# utilidong-ftdi-uart-mk-2_1.net
KiCad netlist of a schematic drawn in EAGLE
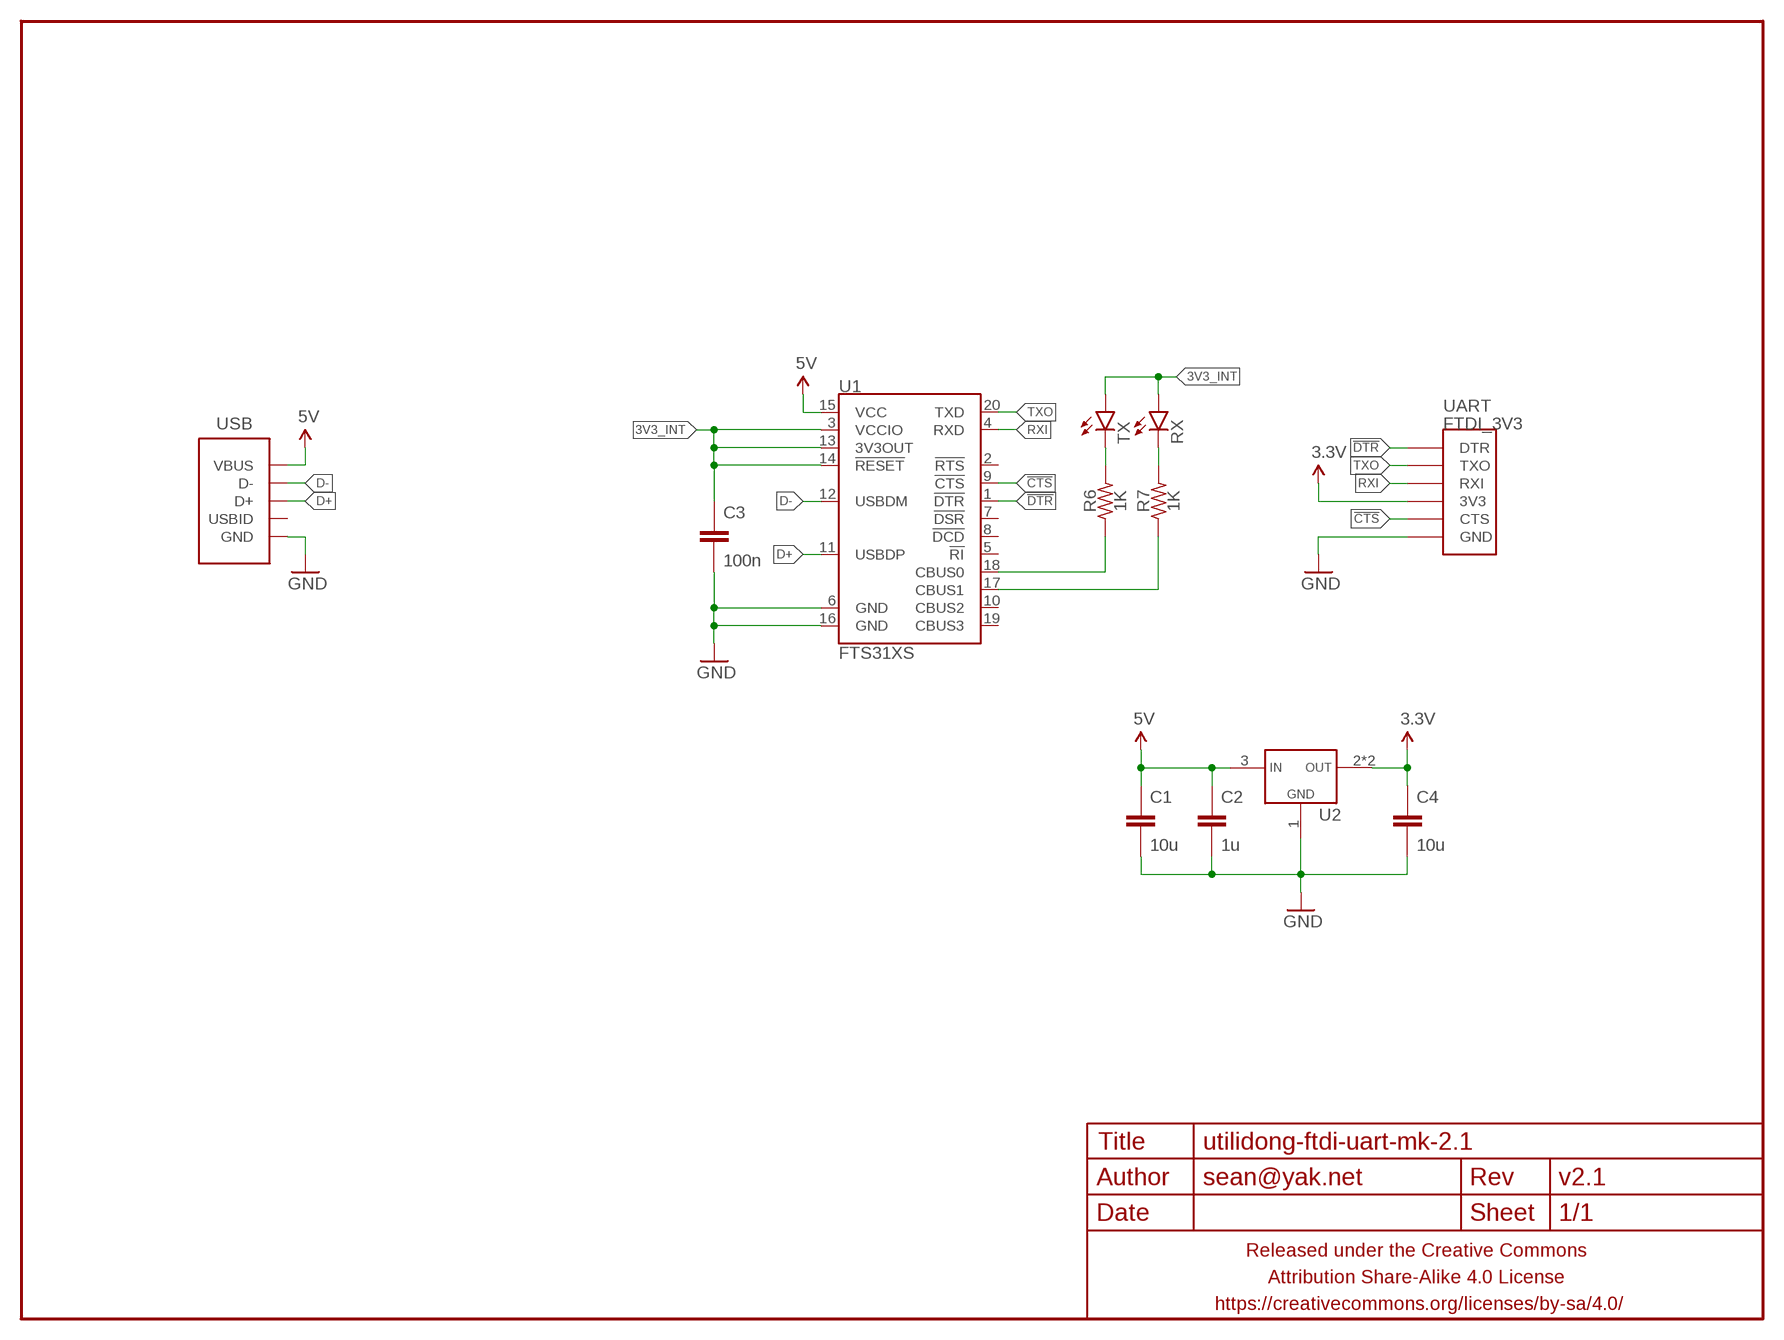
[diagram p0: schematic, sheet 1]

(export (version "E")
  (design (tool "Eeschema 10.0.6"))
  (components
    (comp (ref "C1")
      (value "10u")
      (footprint "eagle-import:C0805")
      (libsource (lib "eagle-import") (part "CAPACITOR-CERAMICC0805"))
    )
    (comp (ref "C2")
      (value "1u")
      (footprint "eagle-import:C0603")
      (libsource (lib "eagle-import") (part "CAPACITOR-CERAMICC0603"))
    )
    (comp (ref "C3")
      (value "100n")
      (footprint "eagle-import:C0603")
      (libsource (lib "eagle-import") (part "CAPACITOR-CERAMICC0603"))
    )
    (comp (ref "C4")
      (value "10u")
      (footprint "eagle-import:C0805")
      (libsource (lib "eagle-import") (part "CAPACITOR-CERAMICC0805"))
    )
    (comp (ref "FRAME1")
      (value "FRAME-LETTERNO_PACKAGE")
      (footprint "eagle-import:DUMMY")
      (fields (field (name "DESIGNER") "sean@yak.net") (field (name "VERSION") "v2.1"))
      (libsource (lib "eagle-import") (part "FRAME-LETTERNO_PACKAGE"))
    )
    (comp (ref "R6")
      (value "1K")
      (footprint "eagle-import:R0603")
      (libsource (lib "eagle-import") (part "RESISTORR0603"))
    )
    (comp (ref "R7")
      (value "1K")
      (footprint "eagle-import:R0603")
      (libsource (lib "eagle-import") (part "RESISTORR0603"))
    )
    (comp (ref "RX")
      (value "LED0603")
      (footprint "eagle-import:LED-0603")
      (libsource (lib "eagle-import") (part "LED0603"))
    )
    (comp (ref "TX")
      (value "LED0603")
      (footprint "eagle-import:LED-0603")
      (libsource (lib "eagle-import") (part "LED0603"))
    )
    (comp (ref "U1")
      (value "FTS31XS")
      (footprint "eagle-import:SSOP20_L")
      (libsource (lib "eagle-import") (part "FT231XS"))
    )
    (comp (ref "U2")
      (value "VREG_1117SOT89")
      (footprint "eagle-import:SOT89")
      (libsource (lib "eagle-import") (part "VREG_1117SOT89"))
    )
    (comp (ref "UART")
      (value "FTDI_3V3")
      (footprint "eagle-import:FTDI_3V3")
      (libsource (lib "eagle-import") (part "FTDI_3V3"))
    )
    (comp (ref "USB")
      (value "USB-ABFCI-10103594-USB-MICRO-B-LESS")
      (footprint "eagle-import:FCI-10103594-USB-MICRO-B-LESS")
      (libsource (lib "eagle-import") (part "USB-ABFCI-10103594-USB-MICRO-B-LESS"))
    )
  )
  (nets
    (net (code "1") (name "/~{CTS}") (class "Default")
      (node (ref "U1") (pin "9") (pinfunction "~{CTS}_9") (pintype "bidirectional"))
      (node (ref "UART") (pin "P$5") (pinfunction "CTS_P$5") (pintype "bidirectional"))
    )
    (net (code "2") (name "/~{DTR}") (class "Default")
      (node (ref "U1") (pin "1") (pinfunction "~{DTR}_1") (pintype "bidirectional"))
      (node (ref "UART") (pin "P$1") (pinfunction "DTR_P$1") (pintype "bidirectional"))
    )
    (net (code "3") (name "3.3V") (class "Default")
      (node (ref "C4") (pin "1") (pinfunction "1_1") (pintype "passive"))
      (node (ref "U2") (pin "2") (pinfunction "VOUT_2") (pintype "bidirectional"))
      (node (ref "U2") (pin "4") (pinfunction "VOUT_4") (pintype "bidirectional"))
      (node (ref "UART") (pin "P$4") (pinfunction "3V3_P$4") (pintype "bidirectional"))
    )
    (net (code "4") (name "3V3_INT") (class "Default")
      (node (ref "C3") (pin "1") (pinfunction "1_1") (pintype "passive"))
      (node (ref "RX") (pin "A") (pinfunction "A_A") (pintype "passive"))
      (node (ref "TX") (pin "A") (pinfunction "A_A") (pintype "passive"))
      (node (ref "U1") (pin "13") (pinfunction "3V3OUT_13") (pintype "bidirectional"))
      (node (ref "U1") (pin "14") (pinfunction "~{RESET}_14") (pintype "bidirectional"))
      (node (ref "U1") (pin "3") (pinfunction "VCCIO_3") (pintype "bidirectional"))
    )
    (net (code "5") (name "5V") (class "Default")
      (node (ref "C1") (pin "1") (pinfunction "1_1") (pintype "passive"))
      (node (ref "C2") (pin "1") (pinfunction "1_1") (pintype "passive"))
      (node (ref "U1") (pin "15") (pinfunction "VCC_15") (pintype "bidirectional"))
      (node (ref "U2") (pin "3") (pinfunction "VIN_3") (pintype "bidirectional"))
      (node (ref "USB") (pin "1") (pinfunction "VBUS_1") (pintype "bidirectional"))
    )
    (net (code "6") (name "D+") (class "Default")
      (node (ref "U1") (pin "11") (pinfunction "USBDP_11") (pintype "bidirectional"))
      (node (ref "USB") (pin "3") (pinfunction "D+_3") (pintype "bidirectional"))
    )
    (net (code "7") (name "D-") (class "Default")
      (node (ref "U1") (pin "12") (pinfunction "USBDM_12") (pintype "bidirectional"))
      (node (ref "USB") (pin "2") (pinfunction "D-_2") (pintype "bidirectional"))
    )
    (net (code "8") (name "GND") (class "Default")
      (node (ref "C1") (pin "2") (pinfunction "2_2") (pintype "passive"))
      (node (ref "C2") (pin "2") (pinfunction "2_2") (pintype "passive"))
      (node (ref "C3") (pin "2") (pinfunction "2_2") (pintype "passive"))
      (node (ref "C4") (pin "2") (pinfunction "2_2") (pintype "passive"))
      (node (ref "U1") (pin "16") (pinfunction "GND_16") (pintype "bidirectional"))
      (node (ref "U1") (pin "6") (pinfunction "GND_6") (pintype "bidirectional"))
      (node (ref "U2") (pin "1") (pinfunction "GND_1") (pintype "bidirectional"))
      (node (ref "UART") (pin "P$6") (pinfunction "GND_P$6") (pintype "bidirectional"))
      (node (ref "USB") (pin "5") (pinfunction "GND_5") (pintype "bidirectional"))
    )
    (net (code "9") (name "Net-(R6-Pad2)") (class "Default")
      (node (ref "R6") (pin "2") (pinfunction "2_2") (pintype "passive"))
      (node (ref "TX") (pin "C") (pinfunction "C_C") (pintype "passive"))
    )
    (net (code "10") (name "Net-(R7-Pad2)") (class "Default")
      (node (ref "R7") (pin "2") (pinfunction "2_2") (pintype "passive"))
      (node (ref "RX") (pin "C") (pinfunction "C_C") (pintype "passive"))
    )
    (net (code "11") (name "Net-(U1-CBUS0)") (class "Default")
      (node (ref "R6") (pin "1") (pinfunction "1_1") (pintype "passive"))
      (node (ref "U1") (pin "18") (pinfunction "CBUS0_18") (pintype "bidirectional"))
    )
    (net (code "12") (name "Net-(U1-CBUS1)") (class "Default")
      (node (ref "R7") (pin "1") (pinfunction "1_1") (pintype "passive"))
      (node (ref "U1") (pin "17") (pinfunction "CBUS1_17") (pintype "bidirectional"))
    )
    (net (code "13") (name "RXI") (class "Default")
      (node (ref "U1") (pin "4") (pinfunction "RXD_4") (pintype "bidirectional"))
      (node (ref "UART") (pin "P$3") (pinfunction "RXI_P$3") (pintype "bidirectional"))
    )
    (net (code "14") (name "TXO") (class "Default")
      (node (ref "U1") (pin "20") (pinfunction "TXD_20") (pintype "bidirectional"))
      (node (ref "UART") (pin "P$2") (pinfunction "TXO_P$2") (pintype "bidirectional"))
    )
    (net (code "15") (name "unconnected-(U1-CBUS2-Pad10)") (class "Default")
      (node (ref "U1") (pin "10") (pinfunction "CBUS2_10") (pintype "bidirectional"))
    )
    (net (code "16") (name "unconnected-(U1-CBUS3-Pad19)") (class "Default")
      (node (ref "U1") (pin "19") (pinfunction "CBUS3_19") (pintype "bidirectional"))
    )
    (net (code "17") (name "unconnected-(U1-~{DCD}-Pad8)") (class "Default")
      (node (ref "U1") (pin "8") (pinfunction "~{DCD}_8") (pintype "bidirectional"))
    )
    (net (code "18") (name "unconnected-(U1-~{DSR}-Pad7)") (class "Default")
      (node (ref "U1") (pin "7") (pinfunction "~{DSR}_7") (pintype "bidirectional"))
    )
    (net (code "19") (name "unconnected-(U1-~{RI}-Pad5)") (class "Default")
      (node (ref "U1") (pin "5") (pinfunction "~{RI}_5") (pintype "bidirectional"))
    )
    (net (code "20") (name "unconnected-(U1-~{RTS}-Pad2)") (class "Default")
      (node (ref "U1") (pin "2") (pinfunction "~{RTS}_2") (pintype "bidirectional"))
    )
    (net (code "21") (name "unconnected-(USB-USBID-Pad4)") (class "Default")
      (node (ref "USB") (pin "4") (pinfunction "USBID_4") (pintype "bidirectional"))
    )
  )
)
